# ProProject_Access_Control_EEPROM_Program.net
KiCad netlist of a schematic drawn in EasyEDA Pro
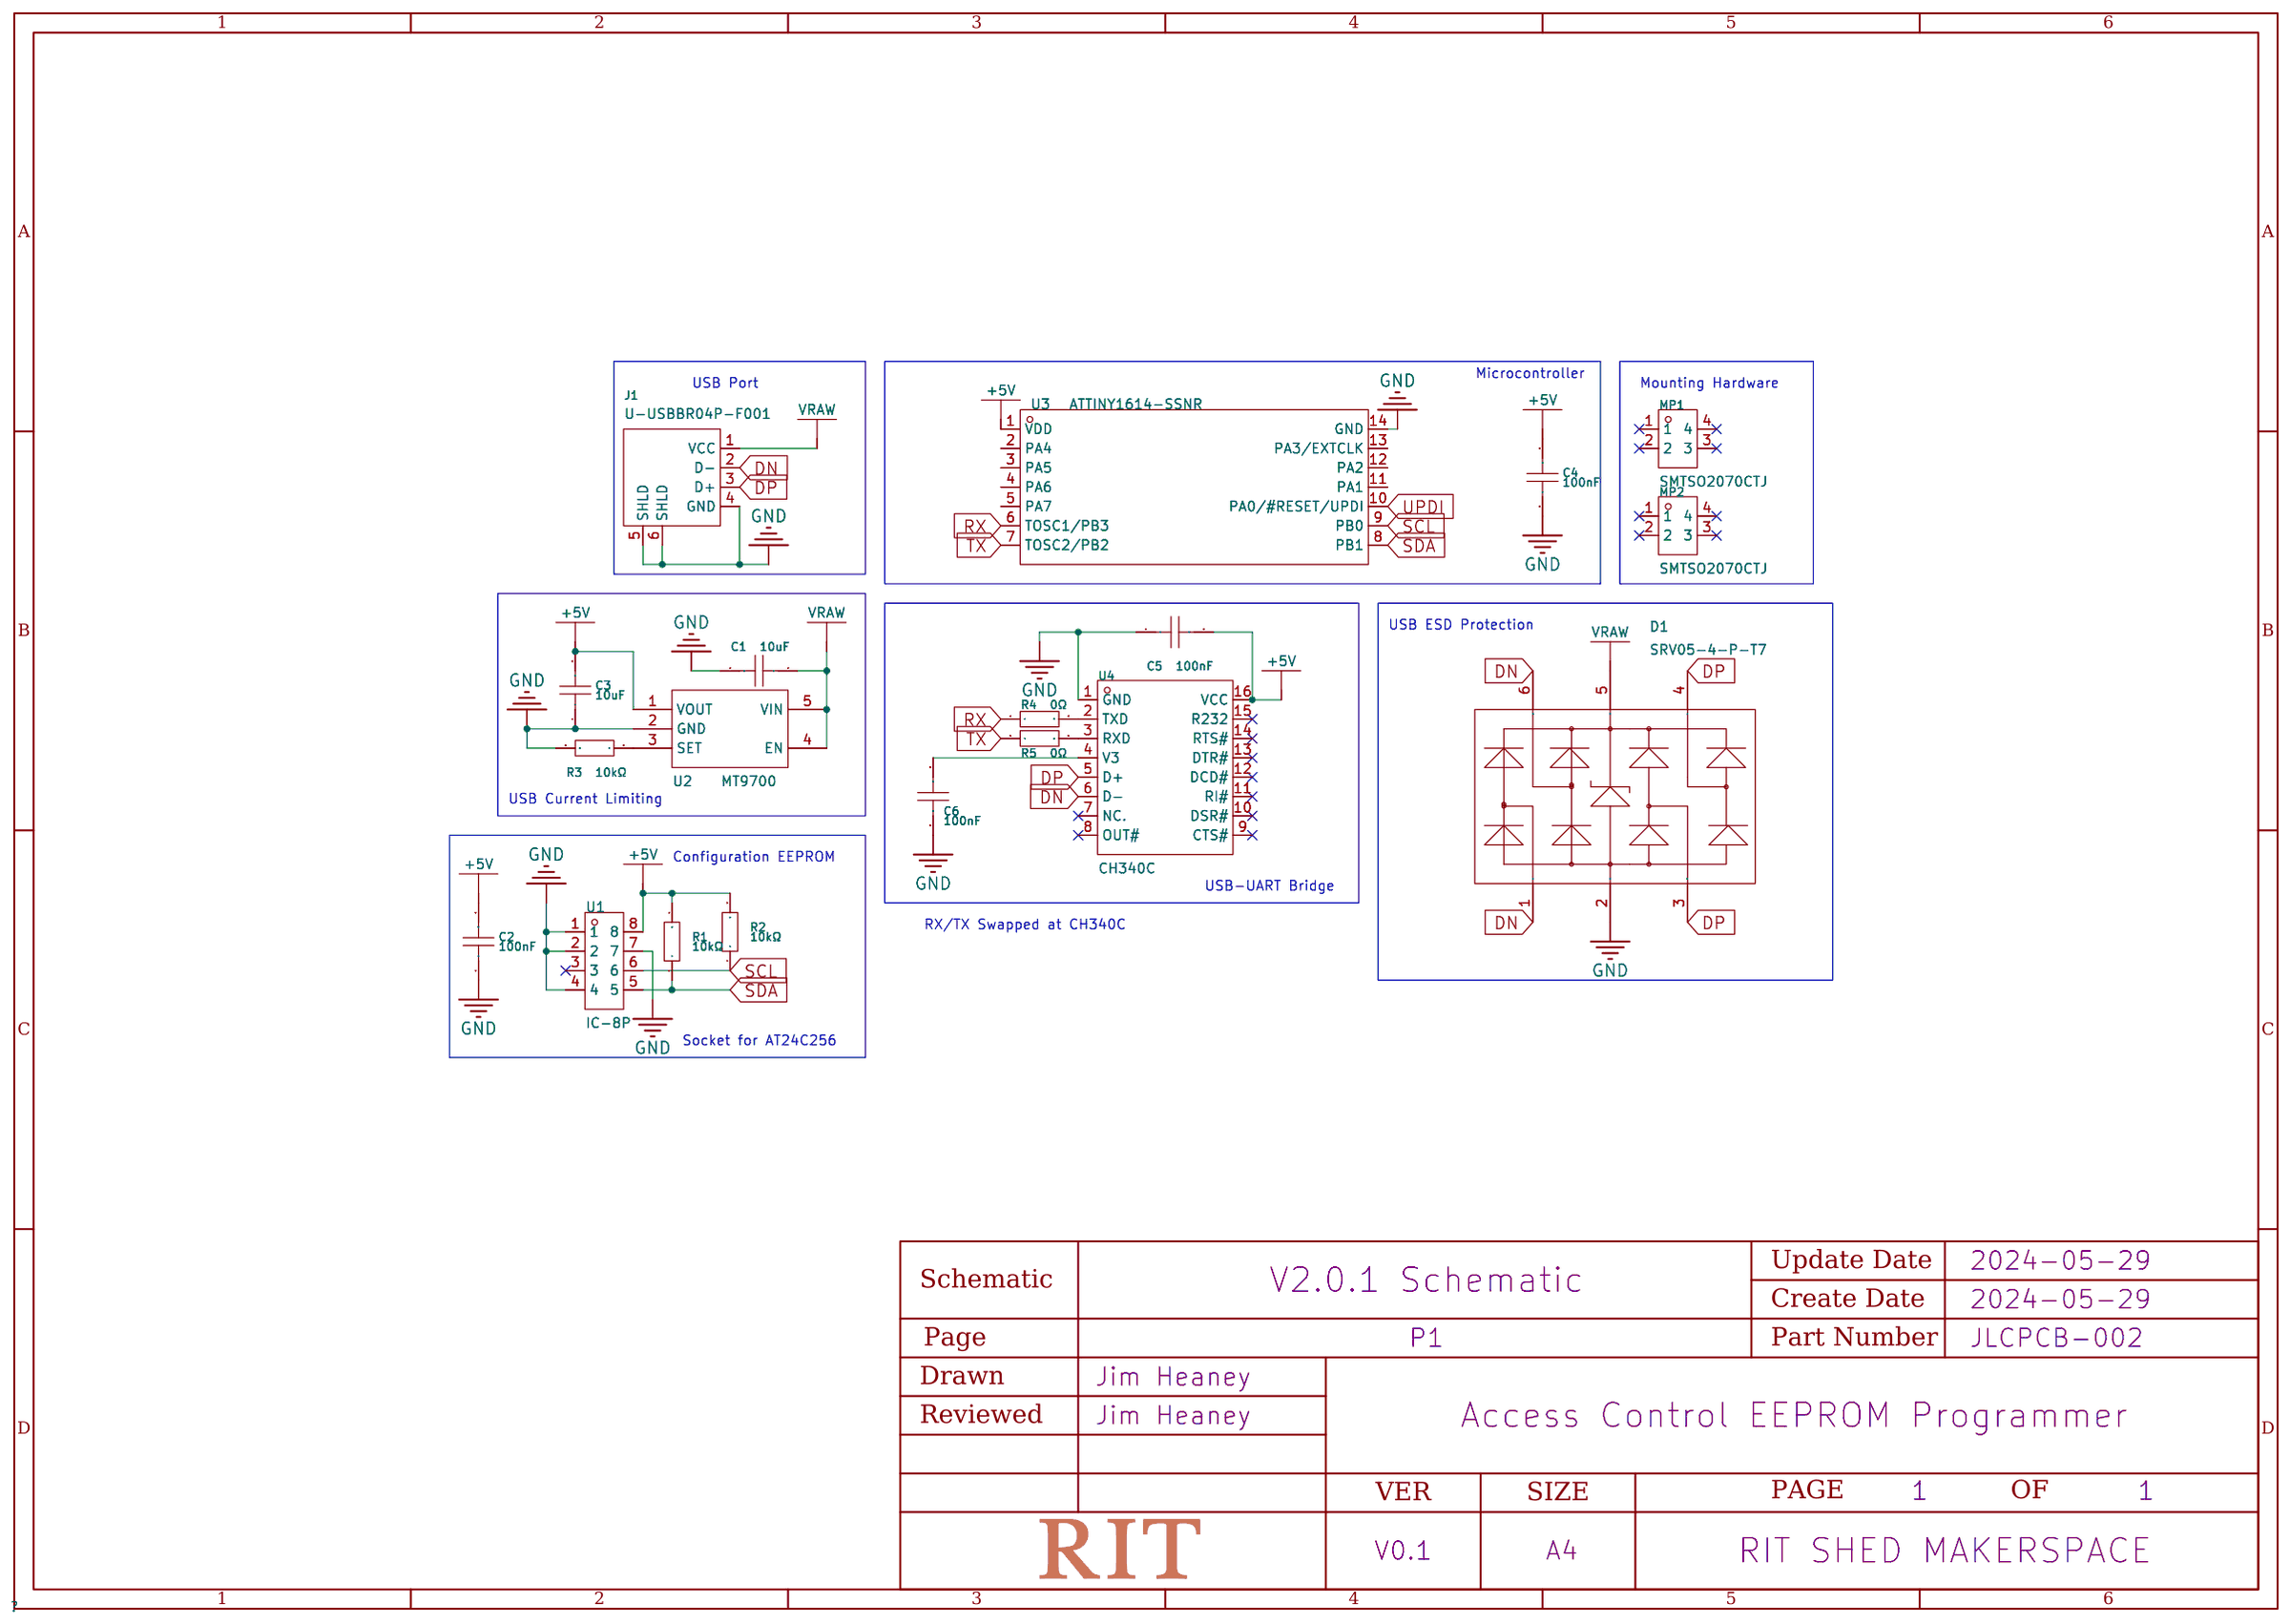
[diagram p0: schematic sheet]

(export (version "E")
  (design (tool "Eeschema 10.0.6"))
  (components
    (comp (ref "C1")
      (value "10uF")
      (footprint "easyedapro:C0603")
      (fields
        (field (name "Manufacturer Part") "CL10A106MA8NRNC")
        (field (name "Manufacturer") "SAMSUNG(三星)")
      )
      (libsource (lib "easyedapro") (part "CL10A106MA8NRNC"))
    )
    (comp (ref "C2")
      (value "100nF")
      (footprint "easyedapro:C0603")
      (fields
        (field (name "Manufacturer Part") "CC0603KRX7R9BB104")
        (field (name "Manufacturer") "YAGEO(国巨)")
      )
      (libsource (lib "easyedapro") (part "CC0603KRX7R9BB104"))
    )
    (comp (ref "C3")
      (value "10uF")
      (footprint "easyedapro:C0603")
      (fields
        (field (name "Manufacturer Part") "CL10A106MA8NRNC")
        (field (name "Manufacturer") "SAMSUNG(三星)")
      )
      (libsource (lib "easyedapro") (part "CL10A106MA8NRNC"))
    )
    (comp (ref "C4")
      (value "100nF")
      (footprint "easyedapro:C0603")
      (fields
        (field (name "Manufacturer Part") "CC0603KRX7R9BB104")
        (field (name "Manufacturer") "YAGEO(国巨)")
      )
      (libsource (lib "easyedapro") (part "CC0603KRX7R9BB104"))
    )
    (comp (ref "C5")
      (value "100nF")
      (footprint "easyedapro:C0603")
      (fields
        (field (name "Manufacturer Part") "CC0603KRX7R9BB104")
        (field (name "Manufacturer") "YAGEO(国巨)")
      )
      (libsource (lib "easyedapro") (part "CC0603KRX7R9BB104"))
    )
    (comp (ref "C6")
      (value "100nF")
      (footprint "easyedapro:C0603")
      (fields
        (field (name "Manufacturer Part") "CC0603KRX7R9BB104")
        (field (name "Manufacturer") "YAGEO(国巨)")
      )
      (libsource (lib "easyedapro") (part "CC0603KRX7R9BB104"))
    )
    (comp (ref "D1")
      (value "SRV05-4-P-T7")
      (footprint "easyedapro:SOT-23-6_L2.9-W1.6-P0.95-LS2.8-BR")
      (fields (field (name "Manufacturer") "PROTEK"))
      (libsource (lib "easyedapro") (part "SRV05-4-P-T7"))
    )
    (comp (ref "J1")
      (value "U-USBBR04P-F001")
      (footprint "easyedapro:USB-B-TH_U241-041N-1BR85-1")
      (fields (field (name "Manufacturer") "Ckmtw(灿科盟)"))
      (libsource (lib "easyedapro") (part "U-USBBR04P-F001"))
    )
    (comp (ref "MP1")
      (value "SMTSO2070CTJ")
      (footprint "easyedapro:SMD_BD5.6-L5.6-W5.6-D3.6")
      (fields (field (name "Manufacturer") "Sinhoo(雄和远景)"))
      (libsource (lib "easyedapro") (part "SMTSO2070CTJ"))
    )
    (comp (ref "MP2")
      (value "SMTSO2070CTJ")
      (footprint "easyedapro:SMD_BD5.6-L5.6-W5.6-D3.6")
      (fields (field (name "Manufacturer") "Sinhoo(雄和远景)"))
      (libsource (lib "easyedapro") (part "SMTSO2070CTJ"))
    )
    (comp (ref "R1")
      (value "10kΩ")
      (footprint "easyedapro:R0603")
      (fields
        (field (name "Manufacturer Part") "0603WAF1002T5E")
        (field (name "Manufacturer") "UNI-ROYAL(厚声)")
      )
      (libsource (lib "easyedapro") (part "0603WAF1002T5E"))
    )
    (comp (ref "R2")
      (value "10kΩ")
      (footprint "easyedapro:R0603")
      (fields
        (field (name "Manufacturer Part") "0603WAF1002T5E")
        (field (name "Manufacturer") "UNI-ROYAL(厚声)")
      )
      (libsource (lib "easyedapro") (part "0603WAF1002T5E"))
    )
    (comp (ref "R3")
      (value "10kΩ")
      (footprint "easyedapro:R0603")
      (fields
        (field (name "Manufacturer Part") "0603WAF1002T5E")
        (field (name "Manufacturer") "UNI-ROYAL(厚声)")
      )
      (libsource (lib "easyedapro") (part "0603WAF1002T5E"))
    )
    (comp (ref "R4")
      (value "0Ω")
      (footprint "easyedapro:R1206")
      (fields
        (field (name "Manufacturer Part") "1206W4F0000T5E")
        (field (name "Manufacturer") "UNI-ROYAL(厚声)")
      )
      (libsource (lib "easyedapro") (part "1206W4F0000T5E"))
    )
    (comp (ref "R5")
      (value "0Ω")
      (footprint "easyedapro:R1206")
      (fields
        (field (name "Manufacturer Part") "1206W4F0000T5E")
        (field (name "Manufacturer") "UNI-ROYAL(厚声)")
      )
      (libsource (lib "easyedapro") (part "1206W4F0000T5E"))
    )
    (comp (ref "U1")
      (value "IC-8P")
      (footprint "easyedapro:DIP-8_L10.2-W10.1-P2.54-LS7.6-BL")
      (description "Number of Positions:8P")
      (fields (field (name "Manufacturer") "ZHOURI(洲日)"))
      (libsource (lib "easyedapro") (part "IC-8P"))
    )
    (comp (ref "U2")
      (value "MT9700")
      (footprint "easyedapro:SOT-23-5_L3.0-W1.7-P0.95-LS2.8-BR")
      (fields (field (name "Manufacturer") "西安航天民芯"))
      (libsource (lib "easyedapro") (part "MT9700"))
    )
    (comp (ref "U3")
      (value "ATTINY1614-SSNR")
      (footprint "easyedapro:SOIC-14_L8.7-W3.9-P1.27-LS6.0-BL")
      (fields (field (name "Manufacturer") "MICROCHIP(美国微芯)"))
      (libsource (lib "easyedapro") (part "ATTINY1614-SSNR"))
    )
    (comp (ref "U4")
      (value "CH340C")
      (footprint "easyedapro:SOP-16_L10.0-W3.9-P1.27-LS6.0-BL")
      (fields (field (name "Manufacturer") "WCH(南京沁恒)"))
      (libsource (lib "easyedapro") (part "CH340C"))
    )
  )
  (nets
    (net (code "1") (name "+5V") (class "Default")
      (node (ref "C2") (pin "2") (pinfunction "2_2") (pintype "input"))
      (node (ref "C3") (pin "2") (pinfunction "2_2") (pintype "input"))
      (node (ref "C4") (pin "2") (pinfunction "2_2") (pintype "input"))
      (node (ref "C5") (pin "2") (pinfunction "2_2") (pintype "input"))
      (node (ref "R1") (pin "2") (pinfunction "2_2") (pintype "input"))
      (node (ref "R2") (pin "2") (pinfunction "2_2") (pintype "input"))
      (node (ref "U1") (pin "8") (pinfunction "8_8") (pintype "unspecified"))
      (node (ref "U2") (pin "1") (pinfunction "VOUT_1") (pintype "unspecified"))
      (node (ref "U3") (pin "1") (pinfunction "VDD_1") (pintype "input"))
      (node (ref "U4") (pin "16") (pinfunction "VCC_16") (pintype "input"))
    )
    (net (code "2") (name "DN") (class "Default")
      (node (ref "D1") (pin "1") (pinfunction "1_1") (pintype "input"))
      (node (ref "D1") (pin "6") (pinfunction "6_6") (pintype "input"))
      (node (ref "J1") (pin "2") (pinfunction "D-_2") (pintype "input"))
      (node (ref "U4") (pin "6") (pinfunction "D-_6") (pintype "input"))
    )
    (net (code "3") (name "DP") (class "Default")
      (node (ref "D1") (pin "3") (pinfunction "3_3") (pintype "input"))
      (node (ref "D1") (pin "4") (pinfunction "4_4") (pintype "input"))
      (node (ref "J1") (pin "3") (pinfunction "D+_3") (pintype "input"))
      (node (ref "U4") (pin "5") (pinfunction "D+_5") (pintype "input"))
    )
    (net (code "4") (name "GND") (class "Default")
      (node (ref "C1") (pin "2") (pinfunction "2_2") (pintype "input"))
      (node (ref "C2") (pin "1") (pinfunction "1_1") (pintype "input"))
      (node (ref "C3") (pin "1") (pinfunction "1_1") (pintype "input"))
      (node (ref "C4") (pin "1") (pinfunction "1_1") (pintype "input"))
      (node (ref "C5") (pin "1") (pinfunction "1_1") (pintype "input"))
      (node (ref "C6") (pin "1") (pinfunction "1_1") (pintype "input"))
      (node (ref "D1") (pin "2") (pinfunction "2_2") (pintype "input"))
      (node (ref "J1") (pin "4") (pinfunction "GND_4") (pintype "input"))
      (node (ref "J1") (pin "5") (pinfunction "SHLD_5") (pintype "input"))
      (node (ref "J1") (pin "6") (pinfunction "SHLD_6") (pintype "input"))
      (node (ref "R3") (pin "2") (pinfunction "2_2") (pintype "input"))
      (node (ref "U1") (pin "1") (pinfunction "1_1") (pintype "unspecified"))
      (node (ref "U1") (pin "2") (pinfunction "2_2") (pintype "unspecified"))
      (node (ref "U1") (pin "4") (pinfunction "4_4") (pintype "unspecified"))
      (node (ref "U1") (pin "7") (pinfunction "7_7") (pintype "unspecified"))
      (node (ref "U2") (pin "2") (pinfunction "GND_2") (pintype "unspecified"))
      (node (ref "U3") (pin "14") (pinfunction "GND_14") (pintype "input"))
      (node (ref "U4") (pin "1") (pinfunction "GND_1") (pintype "input"))
    )
    (net (code "5") (name "Net-(U2-SET)") (class "Default")
      (node (ref "R3") (pin "1") (pinfunction "1_1") (pintype "input"))
      (node (ref "U2") (pin "3") (pinfunction "SET_3") (pintype "unspecified"))
    )
    (net (code "6") (name "Net-(U4-RXD)") (class "Default")
      (node (ref "R5") (pin "2") (pinfunction "2_2") (pintype "input"))
      (node (ref "U4") (pin "3") (pinfunction "RXD_3") (pintype "input"))
    )
    (net (code "7") (name "Net-(U4-TXD)") (class "Default")
      (node (ref "R4") (pin "2") (pinfunction "2_2") (pintype "input"))
      (node (ref "U4") (pin "2") (pinfunction "TXD_2") (pintype "input"))
    )
    (net (code "8") (name "Net-(U4-V3)") (class "Default")
      (node (ref "C6") (pin "2") (pinfunction "2_2") (pintype "input"))
      (node (ref "U4") (pin "4") (pinfunction "V3_4") (pintype "input"))
    )
    (net (code "9") (name "RX") (class "Default")
      (node (ref "R4") (pin "1") (pinfunction "1_1") (pintype "input"))
      (node (ref "U3") (pin "6") (pinfunction "TOSC1/PB3_6") (pintype "input"))
    )
    (net (code "10") (name "SCL") (class "Default")
      (node (ref "R2") (pin "1") (pinfunction "1_1") (pintype "input"))
      (node (ref "U1") (pin "6") (pinfunction "6_6") (pintype "unspecified"))
      (node (ref "U3") (pin "9") (pinfunction "PB0_9") (pintype "input"))
    )
    (net (code "11") (name "SDA") (class "Default")
      (node (ref "R1") (pin "1") (pinfunction "1_1") (pintype "input"))
      (node (ref "U1") (pin "5") (pinfunction "5_5") (pintype "unspecified"))
      (node (ref "U3") (pin "8") (pinfunction "PB1_8") (pintype "input"))
    )
    (net (code "12") (name "TX") (class "Default")
      (node (ref "R5") (pin "1") (pinfunction "1_1") (pintype "input"))
      (node (ref "U3") (pin "7") (pinfunction "TOSC2/PB2_7") (pintype "input"))
    )
    (net (code "13") (name "UPDI") (class "Default")
      (node (ref "U3") (pin "10") (pinfunction "PA0/#RESET/UPDI_10") (pintype "input"))
    )
    (net (code "14") (name "VRAW") (class "Default")
      (node (ref "C1") (pin "1") (pinfunction "1_1") (pintype "input"))
      (node (ref "D1") (pin "5") (pinfunction "5_5") (pintype "input"))
      (node (ref "J1") (pin "1") (pinfunction "VCC_1") (pintype "input"))
      (node (ref "U2") (pin "4") (pinfunction "EN_4") (pintype "unspecified"))
      (node (ref "U2") (pin "5") (pinfunction "VIN_5") (pintype "unspecified"))
    )
    (net (code "15") (name "unconnected-(MP1-Pad1)") (class "Default")
      (node (ref "MP1") (pin "1") (pinfunction "1_1") (pintype "input+no_connect"))
    )
    (net (code "16") (name "unconnected-(MP1-Pad2)") (class "Default")
      (node (ref "MP1") (pin "2") (pinfunction "2_2") (pintype "input+no_connect"))
    )
    (net (code "17") (name "unconnected-(MP1-Pad3)") (class "Default")
      (node (ref "MP1") (pin "3") (pinfunction "3_3") (pintype "input+no_connect"))
    )
    (net (code "18") (name "unconnected-(MP1-Pad4)") (class "Default")
      (node (ref "MP1") (pin "4") (pinfunction "4_4") (pintype "input+no_connect"))
    )
    (net (code "19") (name "unconnected-(MP2-Pad1)") (class "Default")
      (node (ref "MP2") (pin "1") (pinfunction "1_1") (pintype "input+no_connect"))
    )
    (net (code "20") (name "unconnected-(MP2-Pad2)") (class "Default")
      (node (ref "MP2") (pin "2") (pinfunction "2_2") (pintype "input+no_connect"))
    )
    (net (code "21") (name "unconnected-(MP2-Pad3)") (class "Default")
      (node (ref "MP2") (pin "3") (pinfunction "3_3") (pintype "input+no_connect"))
    )
    (net (code "22") (name "unconnected-(MP2-Pad4)") (class "Default")
      (node (ref "MP2") (pin "4") (pinfunction "4_4") (pintype "input+no_connect"))
    )
    (net (code "23") (name "unconnected-(U1-Pad3)") (class "Default")
      (node (ref "U1") (pin "3") (pinfunction "3_3") (pintype "unspecified+no_connect"))
    )
    (net (code "24") (name "unconnected-(U3-PA1-Pad11)") (class "Default")
      (node (ref "U3") (pin "11") (pinfunction "PA1_11") (pintype "input"))
    )
    (net (code "25") (name "unconnected-(U3-PA2-Pad12)") (class "Default")
      (node (ref "U3") (pin "12") (pinfunction "PA2_12") (pintype "input"))
    )
    (net (code "26") (name "unconnected-(U3-PA3{slash}EXTCLK-Pad13)") (class "Default")
      (node (ref "U3") (pin "13") (pinfunction "PA3/EXTCLK_13") (pintype "input"))
    )
    (net (code "27") (name "unconnected-(U3-PA4-Pad2)") (class "Default")
      (node (ref "U3") (pin "2") (pinfunction "PA4_2") (pintype "input"))
    )
    (net (code "28") (name "unconnected-(U3-PA5-Pad3)") (class "Default")
      (node (ref "U3") (pin "3") (pinfunction "PA5_3") (pintype "input"))
    )
    (net (code "29") (name "unconnected-(U3-PA6-Pad4)") (class "Default")
      (node (ref "U3") (pin "4") (pinfunction "PA6_4") (pintype "input"))
    )
    (net (code "30") (name "unconnected-(U3-PA7-Pad5)") (class "Default")
      (node (ref "U3") (pin "5") (pinfunction "PA7_5") (pintype "input"))
    )
    (net (code "31") (name "unconnected-(U4-CTS#-Pad9)") (class "Default")
      (node (ref "U4") (pin "9") (pinfunction "CTS#_9") (pintype "input+no_connect"))
    )
    (net (code "32") (name "unconnected-(U4-DCD#-Pad12)") (class "Default")
      (node (ref "U4") (pin "12") (pinfunction "DCD#_12") (pintype "input+no_connect"))
    )
    (net (code "33") (name "unconnected-(U4-DSR#-Pad10)") (class "Default")
      (node (ref "U4") (pin "10") (pinfunction "DSR#_10") (pintype "input+no_connect"))
    )
    (net (code "34") (name "unconnected-(U4-DTR#-Pad13)") (class "Default")
      (node (ref "U4") (pin "13") (pinfunction "DTR#_13") (pintype "input+no_connect"))
    )
    (net (code "35") (name "unconnected-(U4-NC.-Pad7)") (class "Default")
      (node (ref "U4") (pin "7") (pinfunction "NC._7") (pintype "input+no_connect"))
    )
    (net (code "36") (name "unconnected-(U4-OUT#-Pad8)") (class "Default")
      (node (ref "U4") (pin "8") (pinfunction "OUT#_8") (pintype "input+no_connect"))
    )
    (net (code "37") (name "unconnected-(U4-R232-Pad15)") (class "Default")
      (node (ref "U4") (pin "15") (pinfunction "R232_15") (pintype "input+no_connect"))
    )
    (net (code "38") (name "unconnected-(U4-RI#-Pad11)") (class "Default")
      (node (ref "U4") (pin "11") (pinfunction "RI#_11") (pintype "input+no_connect"))
    )
    (net (code "39") (name "unconnected-(U4-RTS#-Pad14)") (class "Default")
      (node (ref "U4") (pin "14") (pinfunction "RTS#_14") (pintype "input+no_connect"))
    )
  )
)
